# atmega1284_oled.net
KiCad netlist of a schematic drawn in EAGLE
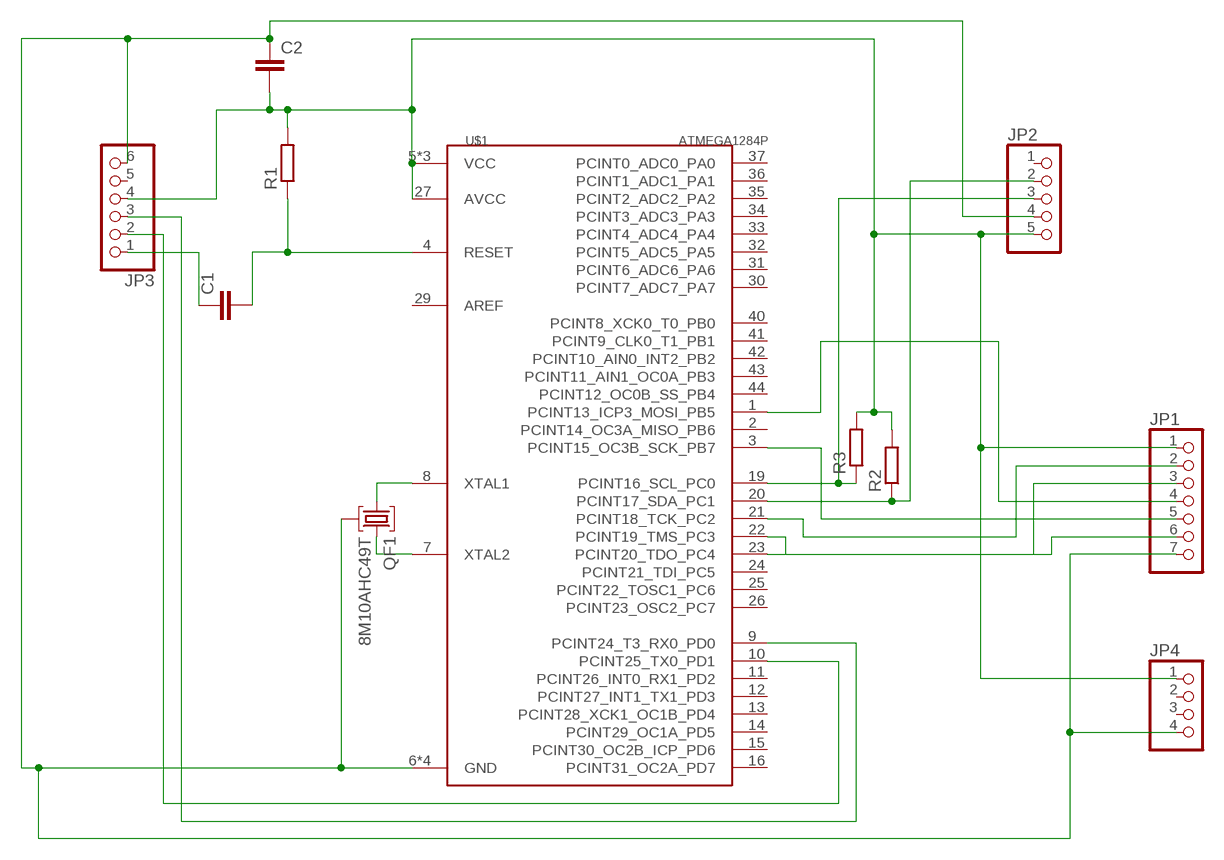
[diagram p0: schematic, sheet 1]

(export (version "E")
  (design (tool "Eeschema 10.0.6"))
  (components
    (comp (ref "C1")
      (value "C-EUC0805")
      (footprint "eagle-import:C0805")
      (libsource (lib "eagle-import") (part "C-EUC0805"))
    )
    (comp (ref "C2")
      (value "C-EUC0805")
      (footprint "eagle-import:C0805")
      (libsource (lib "eagle-import") (part "C-EUC0805"))
    )
    (comp (ref "JP1")
      (value "PINHD-1X7")
      (footprint "eagle-import:1X07")
      (libsource (lib "eagle-import") (part "PINHD-1X7"))
    )
    (comp (ref "JP2")
      (value "PINHD-1X5")
      (footprint "eagle-import:1X05")
      (libsource (lib "eagle-import") (part "PINHD-1X5"))
    )
    (comp (ref "JP3")
      (value "PINHD-1X6")
      (footprint "eagle-import:1X06")
      (libsource (lib "eagle-import") (part "PINHD-1X6"))
    )
    (comp (ref "JP4")
      (value "PINHD-1X4")
      (footprint "eagle-import:1X04")
      (libsource (lib "eagle-import") (part "PINHD-1X4"))
    )
    (comp (ref "QF1")
      (value "8M10AHC49T")
      (footprint "eagle-import:HC49U")
      (libsource (lib "eagle-import") (part "8M10AHC49T"))
    )
    (comp (ref "R1")
      (value "R-EU_R0805")
      (footprint "eagle-import:R0805")
      (libsource (lib "eagle-import") (part "R-EU_R0805"))
    )
    (comp (ref "R2")
      (value "R-EU_R0805")
      (footprint "eagle-import:R0805")
      (libsource (lib "eagle-import") (part "R-EU_R0805"))
    )
    (comp (ref "R3")
      (value "R-EU_R0805")
      (footprint "eagle-import:R0805")
      (libsource (lib "eagle-import") (part "R-EU_R0805"))
    )
    (comp (ref "U$1")
      (value "ATMEGA1284P")
      (footprint "eagle-import:TQFP44")
      (libsource (lib "eagle-import") (part "ATMEGA1284P"))
    )
  )
  (nets
    (net (code "1") (name "Net-(C1-Pad1)") (class "Default")
      (node (ref "C1") (pin "1") (pinfunction "1_1") (pintype "passive"))
      (node (ref "JP3") (pin "1") (pinfunction "1_1") (pintype "passive"))
    )
    (net (code "2") (name "Net-(C2-Pad1)") (class "Default")
      (node (ref "C2") (pin "1") (pinfunction "1_1") (pintype "passive"))
      (node (ref "JP1") (pin "7") (pinfunction "7_7") (pintype "passive"))
      (node (ref "JP2") (pin "4") (pinfunction "4_4") (pintype "passive"))
      (node (ref "JP3") (pin "6") (pinfunction "6_6") (pintype "passive"))
      (node (ref "JP4") (pin "4") (pinfunction "4_4") (pintype "passive"))
      (node (ref "QF1") (pin "2") (pinfunction "2_2") (pintype "passive"))
      (node (ref "U$1") (pin "18") (pinfunction "GND_18") (pintype "bidirectional"))
      (node (ref "U$1") (pin "28") (pinfunction "GND_28") (pintype "bidirectional"))
      (node (ref "U$1") (pin "39") (pinfunction "GND_39") (pintype "bidirectional"))
      (node (ref "U$1") (pin "6") (pinfunction "GND_6") (pintype "bidirectional"))
    )
    (net (code "3") (name "Net-(U$1-AVCC)") (class "Default")
      (node (ref "C2") (pin "2") (pinfunction "2_2") (pintype "passive"))
      (node (ref "JP1") (pin "1") (pinfunction "1_1") (pintype "passive"))
      (node (ref "JP2") (pin "5") (pinfunction "5_5") (pintype "passive"))
      (node (ref "JP3") (pin "4") (pinfunction "4_4") (pintype "passive"))
      (node (ref "JP4") (pin "1") (pinfunction "1_1") (pintype "passive"))
      (node (ref "R1") (pin "2") (pinfunction "2_2") (pintype "passive"))
      (node (ref "R2") (pin "2") (pinfunction "2_2") (pintype "passive"))
      (node (ref "R3") (pin "2") (pinfunction "2_2") (pintype "passive"))
      (node (ref "U$1") (pin "17") (pinfunction "VCC_17") (pintype "bidirectional"))
      (node (ref "U$1") (pin "27") (pinfunction "AVCC_27") (pintype "bidirectional"))
      (node (ref "U$1") (pin "38") (pinfunction "VCC_38") (pintype "bidirectional"))
      (node (ref "U$1") (pin "5") (pinfunction "VCC_5") (pintype "bidirectional"))
    )
    (net (code "4") (name "Net-(U$1-PCINT13_ICP3_MOSI_PB5)") (class "Default")
      (node (ref "JP1") (pin "4") (pinfunction "4_4") (pintype "passive"))
      (node (ref "U$1") (pin "1") (pinfunction "PCINT13_ICP3_MOSI_PB5_1") (pintype "bidirectional"))
    )
    (net (code "5") (name "Net-(U$1-PCINT15_OC3B_SCK_PB7)") (class "Default")
      (node (ref "JP1") (pin "5") (pinfunction "5_5") (pintype "passive"))
      (node (ref "U$1") (pin "3") (pinfunction "PCINT15_OC3B_SCK_PB7_3") (pintype "bidirectional"))
    )
    (net (code "6") (name "Net-(U$1-PCINT16_SCL_PC0)") (class "Default")
      (node (ref "JP2") (pin "3") (pinfunction "3_3") (pintype "passive"))
      (node (ref "R3") (pin "1") (pinfunction "1_1") (pintype "passive"))
      (node (ref "U$1") (pin "19") (pinfunction "PCINT16_SCL_PC0_19") (pintype "bidirectional"))
    )
    (net (code "7") (name "Net-(U$1-PCINT17_SDA_PC1)") (class "Default")
      (node (ref "JP2") (pin "2") (pinfunction "2_2") (pintype "passive"))
      (node (ref "R2") (pin "1") (pinfunction "1_1") (pintype "passive"))
      (node (ref "U$1") (pin "20") (pinfunction "PCINT17_SDA_PC1_20") (pintype "bidirectional"))
    )
    (net (code "8") (name "Net-(U$1-PCINT18_TCK_PC2)") (class "Default")
      (node (ref "JP1") (pin "2") (pinfunction "2_2") (pintype "passive"))
      (node (ref "U$1") (pin "21") (pinfunction "PCINT18_TCK_PC2_21") (pintype "bidirectional"))
    )
    (net (code "9") (name "Net-(U$1-PCINT19_TMS_PC3)") (class "Default")
      (node (ref "JP1") (pin "3") (pinfunction "3_3") (pintype "passive"))
      (node (ref "U$1") (pin "22") (pinfunction "PCINT19_TMS_PC3_22") (pintype "bidirectional"))
    )
    (net (code "10") (name "Net-(U$1-PCINT20_TDO_PC4)") (class "Default")
      (node (ref "JP1") (pin "6") (pinfunction "6_6") (pintype "passive"))
      (node (ref "U$1") (pin "23") (pinfunction "PCINT20_TDO_PC4_23") (pintype "bidirectional"))
    )
    (net (code "11") (name "Net-(U$1-PCINT24_T3_RX0_PD0)") (class "Default")
      (node (ref "JP3") (pin "3") (pinfunction "3_3") (pintype "passive"))
      (node (ref "U$1") (pin "9") (pinfunction "PCINT24_T3_RX0_PD0_9") (pintype "bidirectional"))
    )
    (net (code "12") (name "Net-(U$1-PCINT25_TX0_PD1)") (class "Default")
      (node (ref "JP3") (pin "2") (pinfunction "2_2") (pintype "passive"))
      (node (ref "U$1") (pin "10") (pinfunction "PCINT25_TX0_PD1_10") (pintype "bidirectional"))
    )
    (net (code "13") (name "Net-(U$1-RESET)") (class "Default")
      (node (ref "C1") (pin "2") (pinfunction "2_2") (pintype "passive"))
      (node (ref "R1") (pin "1") (pinfunction "1_1") (pintype "passive"))
      (node (ref "U$1") (pin "4") (pinfunction "RESET_4") (pintype "bidirectional"))
    )
    (net (code "14") (name "Net-(U$1-XTAL1)") (class "Default")
      (node (ref "QF1") (pin "1") (pinfunction "1_1") (pintype "passive"))
      (node (ref "U$1") (pin "8") (pinfunction "XTAL1_8") (pintype "bidirectional"))
    )
    (net (code "15") (name "Net-(U$1-XTAL2)") (class "Default")
      (node (ref "QF1") (pin "3") (pinfunction "3_3") (pintype "passive"))
      (node (ref "U$1") (pin "7") (pinfunction "XTAL2_7") (pintype "bidirectional"))
    )
    (net (code "16") (name "unconnected-(JP2-Pad1)") (class "Default")
      (node (ref "JP2") (pin "1") (pinfunction "1_1") (pintype "passive"))
    )
    (net (code "17") (name "unconnected-(JP3-Pad5)") (class "Default")
      (node (ref "JP3") (pin "5") (pinfunction "5_5") (pintype "passive"))
    )
    (net (code "18") (name "unconnected-(JP4-Pad2)") (class "Default")
      (node (ref "JP4") (pin "2") (pinfunction "2_2") (pintype "passive"))
    )
    (net (code "19") (name "unconnected-(JP4-Pad3)") (class "Default")
      (node (ref "JP4") (pin "3") (pinfunction "3_3") (pintype "passive"))
    )
    (net (code "20") (name "unconnected-(U$1-AREF-Pad29)") (class "Default")
      (node (ref "U$1") (pin "29") (pinfunction "AREF_29") (pintype "bidirectional"))
    )
    (net (code "21") (name "unconnected-(U$1-PCINT0_ADC0_PA0-Pad37)") (class "Default")
      (node (ref "U$1") (pin "37") (pinfunction "PCINT0_ADC0_PA0_37") (pintype "bidirectional"))
    )
    (net (code "22") (name "unconnected-(U$1-PCINT1_ADC1_PA1-Pad36)") (class "Default")
      (node (ref "U$1") (pin "36") (pinfunction "PCINT1_ADC1_PA1_36") (pintype "bidirectional"))
    )
    (net (code "23") (name "unconnected-(U$1-PCINT2_ADC2_PA2-Pad35)") (class "Default")
      (node (ref "U$1") (pin "35") (pinfunction "PCINT2_ADC2_PA2_35") (pintype "bidirectional"))
    )
    (net (code "24") (name "unconnected-(U$1-PCINT3_ADC3_PA3-Pad34)") (class "Default")
      (node (ref "U$1") (pin "34") (pinfunction "PCINT3_ADC3_PA3_34") (pintype "bidirectional"))
    )
    (net (code "25") (name "unconnected-(U$1-PCINT4_ADC4_PA4-Pad33)") (class "Default")
      (node (ref "U$1") (pin "33") (pinfunction "PCINT4_ADC4_PA4_33") (pintype "bidirectional"))
    )
    (net (code "26") (name "unconnected-(U$1-PCINT5_ADC5_PA5-Pad32)") (class "Default")
      (node (ref "U$1") (pin "32") (pinfunction "PCINT5_ADC5_PA5_32") (pintype "bidirectional"))
    )
    (net (code "27") (name "unconnected-(U$1-PCINT6_ADC6_PA6-Pad31)") (class "Default")
      (node (ref "U$1") (pin "31") (pinfunction "PCINT6_ADC6_PA6_31") (pintype "bidirectional"))
    )
    (net (code "28") (name "unconnected-(U$1-PCINT7_ADC7_PA7-Pad30)") (class "Default")
      (node (ref "U$1") (pin "30") (pinfunction "PCINT7_ADC7_PA7_30") (pintype "bidirectional"))
    )
    (net (code "29") (name "unconnected-(U$1-PCINT8_XCK0_T0_PB0-Pad40)") (class "Default")
      (node (ref "U$1") (pin "40") (pinfunction "PCINT8_XCK0_T0_PB0_40") (pintype "bidirectional"))
    )
    (net (code "30") (name "unconnected-(U$1-PCINT9_CLK0_T1_PB1-Pad41)") (class "Default")
      (node (ref "U$1") (pin "41") (pinfunction "PCINT9_CLK0_T1_PB1_41") (pintype "bidirectional"))
    )
    (net (code "31") (name "unconnected-(U$1-PCINT10_AIN0_INT2_PB2-Pad42)") (class "Default")
      (node (ref "U$1") (pin "42") (pinfunction "PCINT10_AIN0_INT2_PB2_42") (pintype "bidirectional"))
    )
    (net (code "32") (name "unconnected-(U$1-PCINT11_AIN1_OC0A_PB3-Pad43)") (class "Default")
      (node (ref "U$1") (pin "43") (pinfunction "PCINT11_AIN1_OC0A_PB3_43") (pintype "bidirectional"))
    )
    (net (code "33") (name "unconnected-(U$1-PCINT12_OC0B_SS_PB4-Pad44)") (class "Default")
      (node (ref "U$1") (pin "44") (pinfunction "PCINT12_OC0B_SS_PB4_44") (pintype "bidirectional"))
    )
    (net (code "34") (name "unconnected-(U$1-PCINT14_OC3A_MISO_PB6-Pad2)") (class "Default")
      (node (ref "U$1") (pin "2") (pinfunction "PCINT14_OC3A_MISO_PB6_2") (pintype "bidirectional"))
    )
    (net (code "35") (name "unconnected-(U$1-PCINT21_TDI_PC5-Pad24)") (class "Default")
      (node (ref "U$1") (pin "24") (pinfunction "PCINT21_TDI_PC5_24") (pintype "bidirectional"))
    )
    (net (code "36") (name "unconnected-(U$1-PCINT22_TOSC1_PC6-Pad25)") (class "Default")
      (node (ref "U$1") (pin "25") (pinfunction "PCINT22_TOSC1_PC6_25") (pintype "bidirectional"))
    )
    (net (code "37") (name "unconnected-(U$1-PCINT23_OSC2_PC7-Pad26)") (class "Default")
      (node (ref "U$1") (pin "26") (pinfunction "PCINT23_OSC2_PC7_26") (pintype "bidirectional"))
    )
    (net (code "38") (name "unconnected-(U$1-PCINT26_INT0_RX1_PD2-Pad11)") (class "Default")
      (node (ref "U$1") (pin "11") (pinfunction "PCINT26_INT0_RX1_PD2_11") (pintype "bidirectional"))
    )
    (net (code "39") (name "unconnected-(U$1-PCINT27_INT1_TX1_PD3-Pad12)") (class "Default")
      (node (ref "U$1") (pin "12") (pinfunction "PCINT27_INT1_TX1_PD3_12") (pintype "bidirectional"))
    )
    (net (code "40") (name "unconnected-(U$1-PCINT28_XCK1_OC1B_PD4-Pad13)") (class "Default")
      (node (ref "U$1") (pin "13") (pinfunction "PCINT28_XCK1_OC1B_PD4_13") (pintype "bidirectional"))
    )
    (net (code "41") (name "unconnected-(U$1-PCINT29_OC1A_PD5-Pad14)") (class "Default")
      (node (ref "U$1") (pin "14") (pinfunction "PCINT29_OC1A_PD5_14") (pintype "bidirectional"))
    )
    (net (code "42") (name "unconnected-(U$1-PCINT30_OC2B_ICP_PD6-Pad15)") (class "Default")
      (node (ref "U$1") (pin "15") (pinfunction "PCINT30_OC2B_ICP_PD6_15") (pintype "bidirectional"))
    )
    (net (code "43") (name "unconnected-(U$1-PCINT31_OC2A_PD7-Pad16)") (class "Default")
      (node (ref "U$1") (pin "16") (pinfunction "PCINT31_OC2A_PD7_16") (pintype "bidirectional"))
    )
  )
)
